# OzarkPinnacle.net
KiCad netlist of a schematic drawn in EAGLE
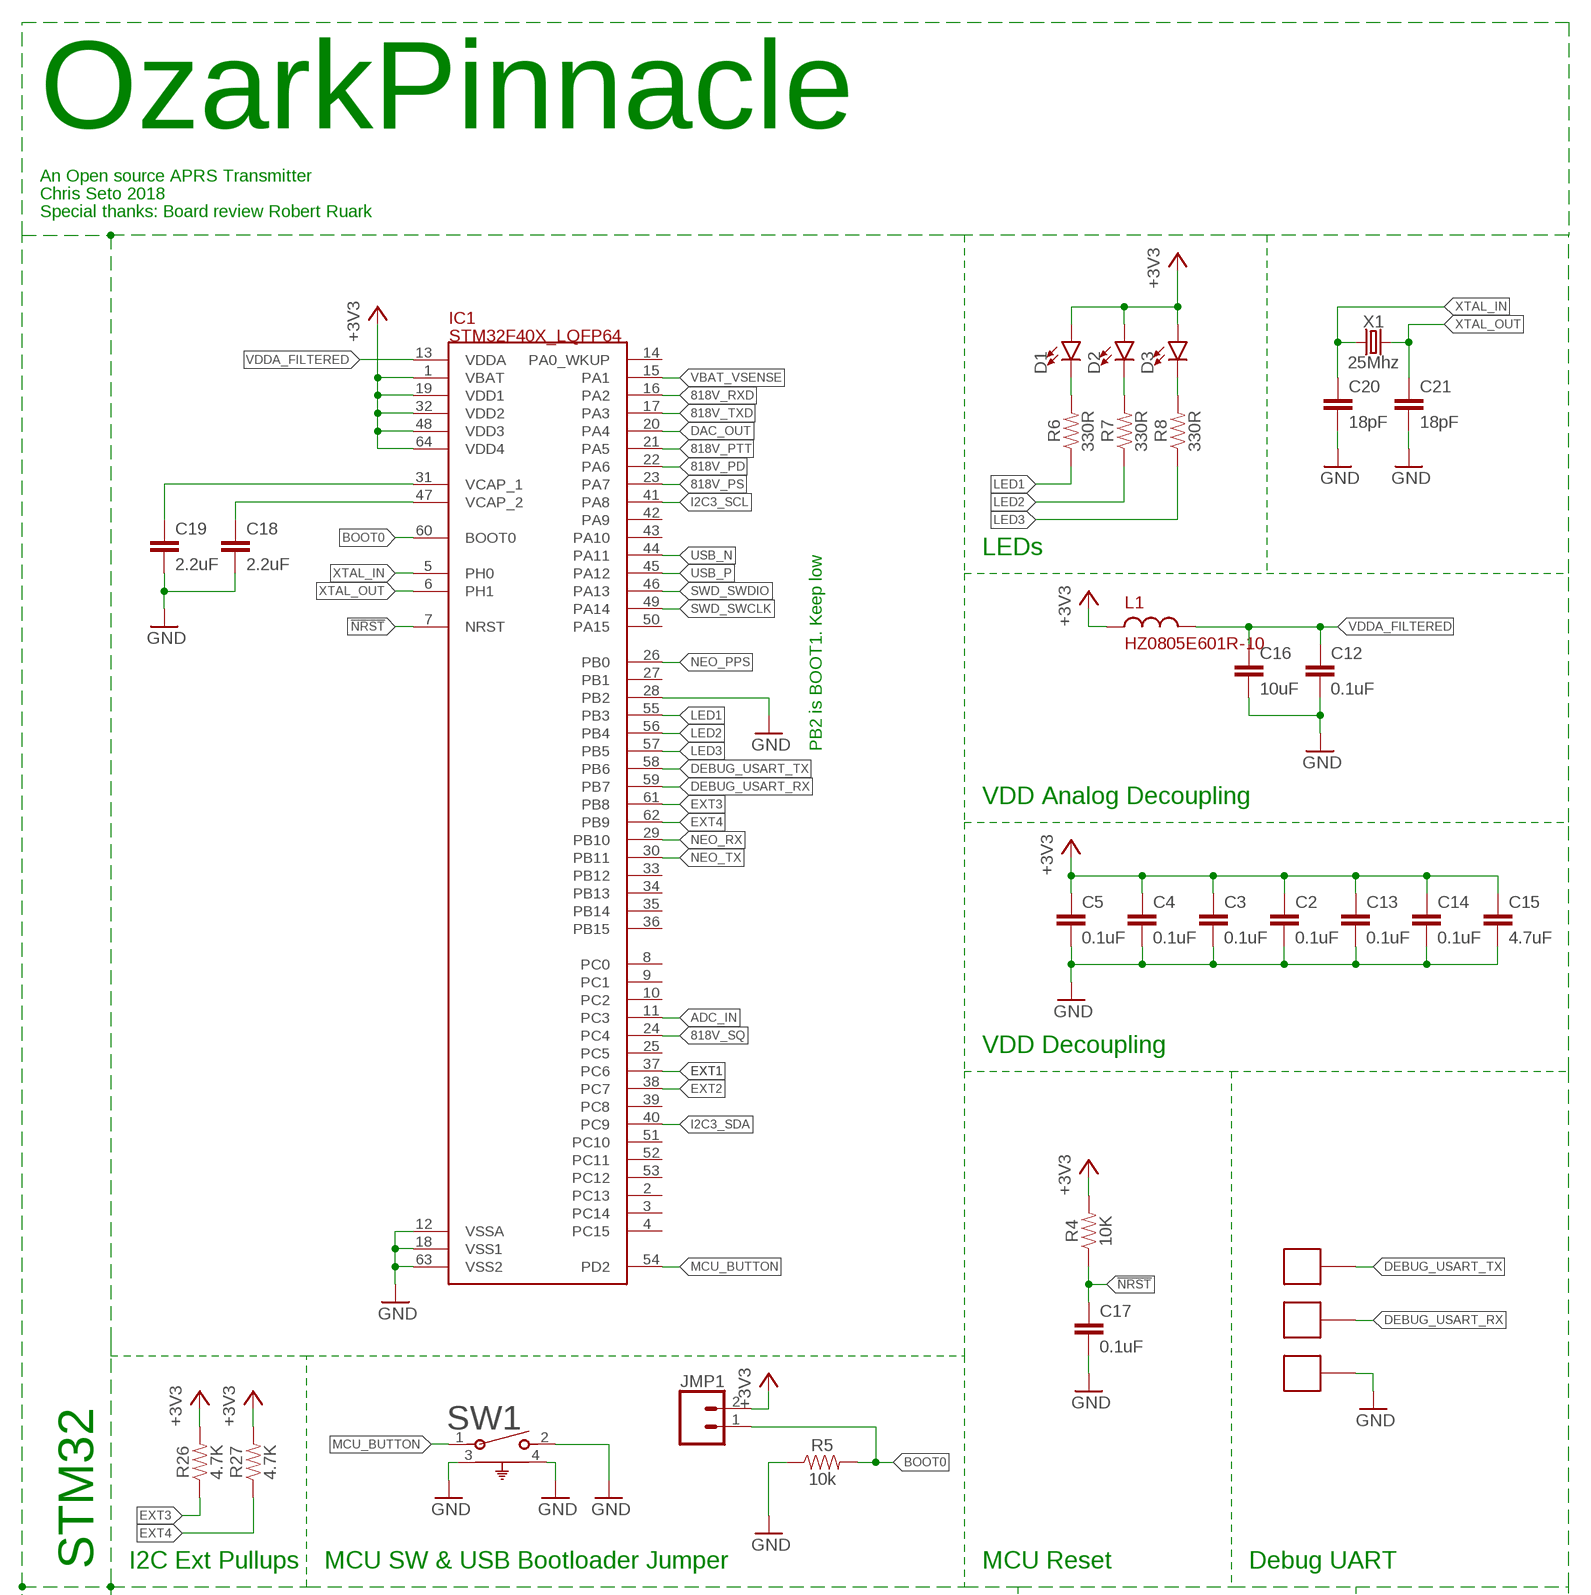
[diagram p0: schematic, sheet 1, part 1 of 2]
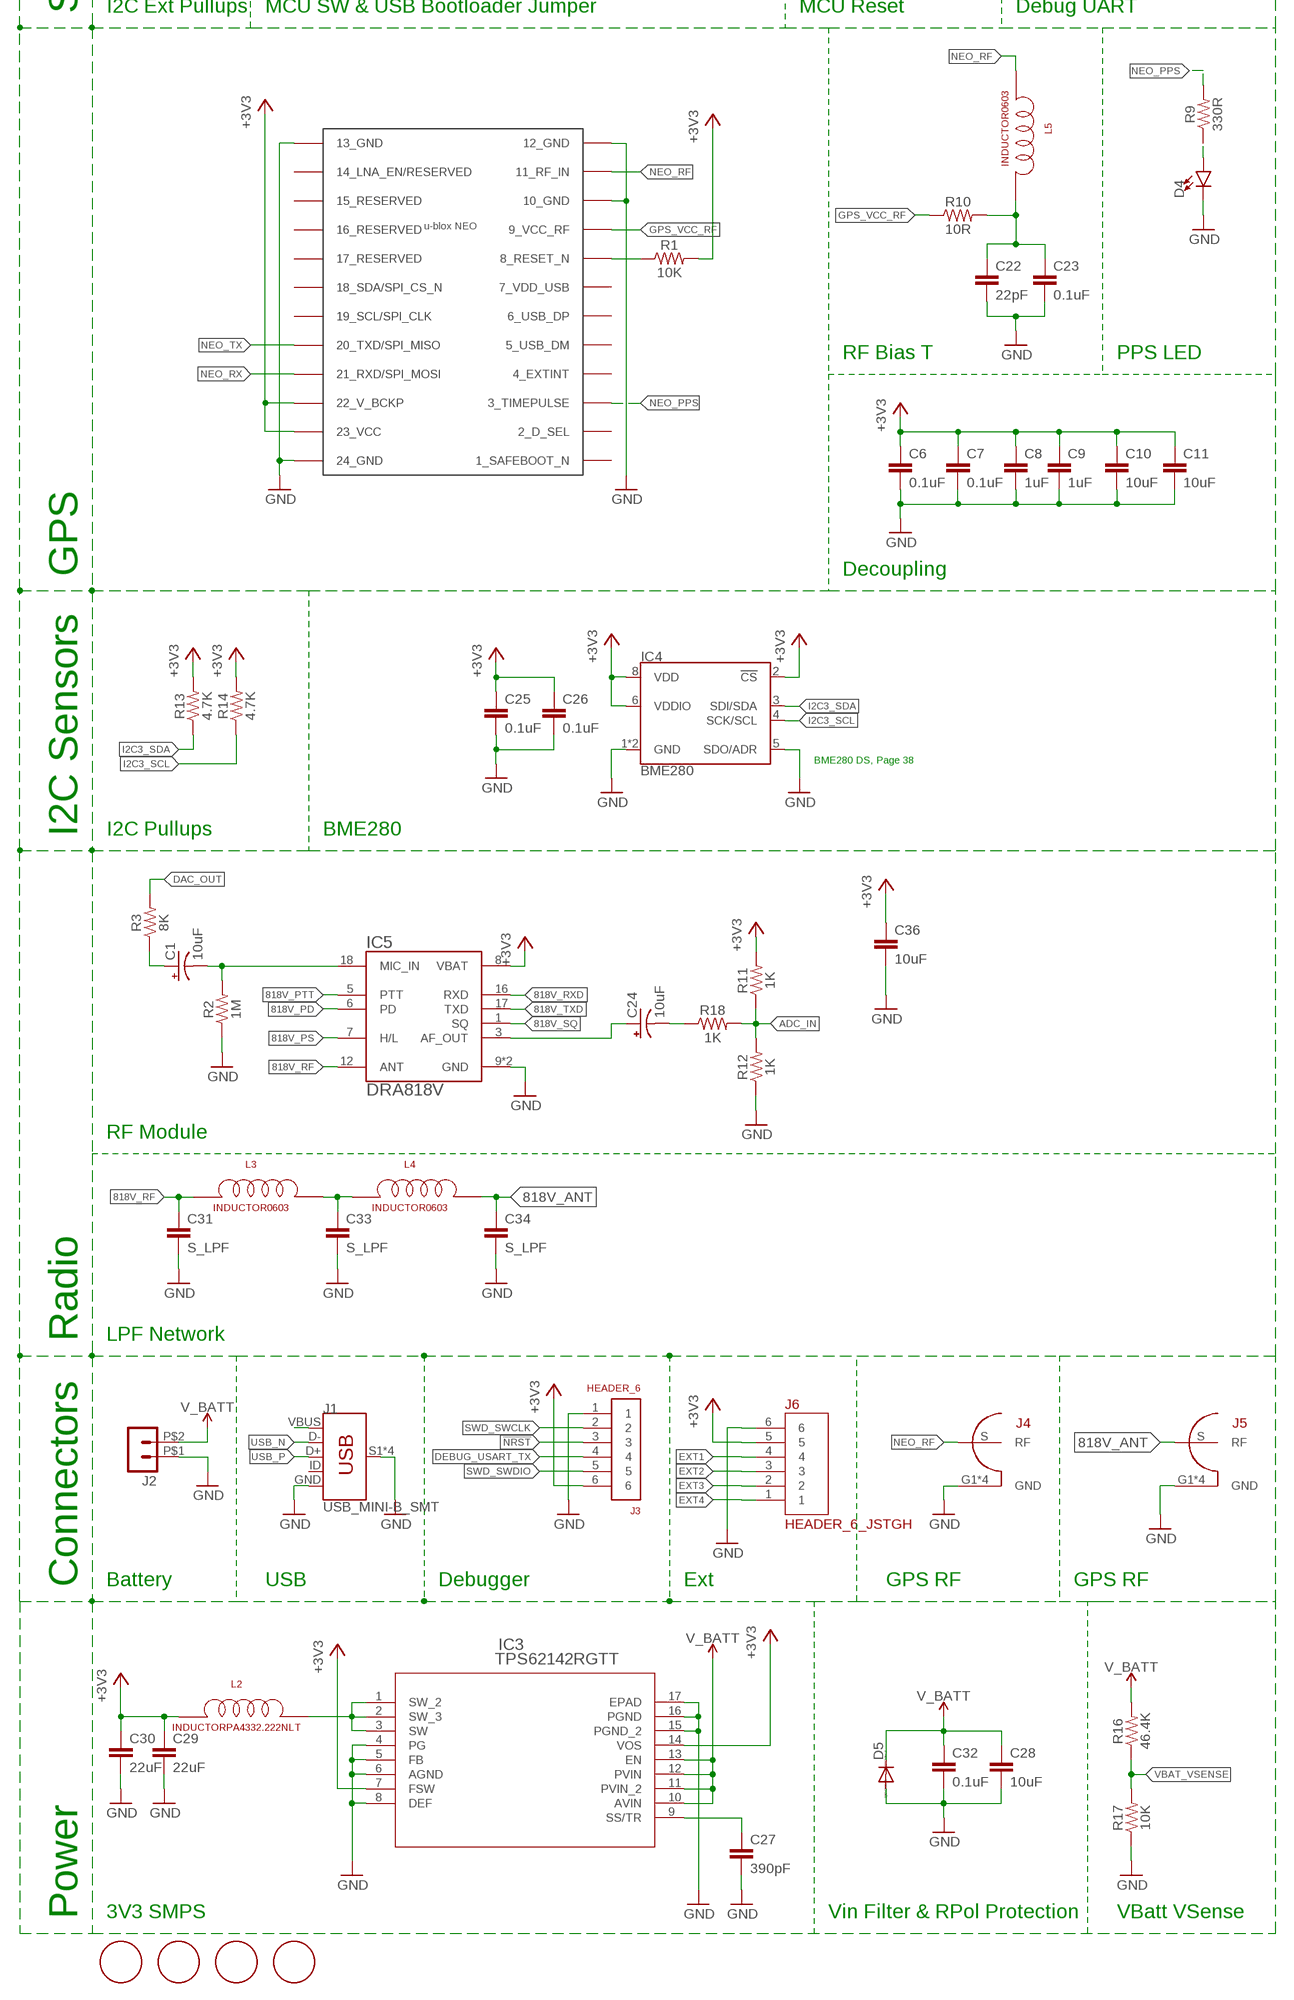
[diagram p1: schematic, sheet 1, part 2 of 2]

(export (version "E")
  (design (tool "Eeschema 10.0.6"))
  (components
    (comp (ref "C1")
      (value "10uF")
      (footprint "eagle-import:1206")
      (libsource (lib "eagle-import") (part "CAP_POL1206_POL"))
    )
    (comp (ref "C2")
      (value "0.1uF")
      (footprint "eagle-import:0603")
      (libsource (lib "eagle-import") (part "CAP0603"))
    )
    (comp (ref "C3")
      (value "0.1uF")
      (footprint "eagle-import:0603")
      (libsource (lib "eagle-import") (part "CAP0603"))
    )
    (comp (ref "C4")
      (value "0.1uF")
      (footprint "eagle-import:0603")
      (libsource (lib "eagle-import") (part "CAP0603"))
    )
    (comp (ref "C5")
      (value "0.1uF")
      (footprint "eagle-import:0603")
      (libsource (lib "eagle-import") (part "CAP0603"))
    )
    (comp (ref "C6")
      (value "0.1uF")
      (footprint "eagle-import:0603")
      (libsource (lib "eagle-import") (part "CAP0603"))
    )
    (comp (ref "C7")
      (value "0.1uF")
      (footprint "eagle-import:0603")
      (libsource (lib "eagle-import") (part "CAP0603"))
    )
    (comp (ref "C8")
      (value "1uF")
      (footprint "eagle-import:C0805")
      (libsource (lib "eagle-import") (part "C-EUC0805"))
    )
    (comp (ref "C9")
      (value "1uF")
      (footprint "eagle-import:C0805")
      (libsource (lib "eagle-import") (part "C-EUC0805"))
    )
    (comp (ref "C10")
      (value "10uF")
      (footprint "eagle-import:C0805")
      (libsource (lib "eagle-import") (part "C-EUC0805"))
    )
    (comp (ref "C11")
      (value "10uF")
      (footprint "eagle-import:C0805")
      (libsource (lib "eagle-import") (part "C-EUC0805"))
    )
    (comp (ref "C12")
      (value "0.1uF")
      (footprint "eagle-import:0603")
      (libsource (lib "eagle-import") (part "CAP0603"))
    )
    (comp (ref "C13")
      (value "0.1uF")
      (footprint "eagle-import:0603")
      (libsource (lib "eagle-import") (part "CAP0603"))
    )
    (comp (ref "C14")
      (value "0.1uF")
      (footprint "eagle-import:0603")
      (libsource (lib "eagle-import") (part "CAP0603"))
    )
    (comp (ref "C15")
      (value "4.7uF")
      (footprint "eagle-import:C0805")
      (libsource (lib "eagle-import") (part "C-EUC0805"))
    )
    (comp (ref "C16")
      (value "10uF")
      (footprint "eagle-import:C0805")
      (libsource (lib "eagle-import") (part "C-EUC0805"))
    )
    (comp (ref "C17")
      (value "0.1uF")
      (footprint "eagle-import:0603")
      (libsource (lib "eagle-import") (part "CAP0603"))
    )
    (comp (ref "C18")
      (value "2.2uF")
      (footprint "eagle-import:C0805")
      (libsource (lib "eagle-import") (part "C-EUC0805"))
    )
    (comp (ref "C19")
      (value "2.2uF")
      (footprint "eagle-import:C0805")
      (libsource (lib "eagle-import") (part "C-EUC0805"))
    )
    (comp (ref "C20")
      (value "18pF")
      (footprint "eagle-import:0603")
      (libsource (lib "eagle-import") (part "CAP0603"))
    )
    (comp (ref "C21")
      (value "18pF")
      (footprint "eagle-import:0603")
      (libsource (lib "eagle-import") (part "CAP0603"))
    )
    (comp (ref "C22")
      (value "22pF")
      (footprint "eagle-import:0603")
      (libsource (lib "eagle-import") (part "CAP0603"))
    )
    (comp (ref "C23")
      (value "0.1uF")
      (footprint "eagle-import:0603")
      (libsource (lib "eagle-import") (part "CAP0603"))
    )
    (comp (ref "C24")
      (value "10uF")
      (footprint "eagle-import:1206")
      (libsource (lib "eagle-import") (part "CAP_POL1206_POL"))
    )
    (comp (ref "C25")
      (value "0.1uF")
      (footprint "eagle-import:0603")
      (libsource (lib "eagle-import") (part "CAP0603"))
    )
    (comp (ref "C26")
      (value "0.1uF")
      (footprint "eagle-import:0603")
      (libsource (lib "eagle-import") (part "CAP0603"))
    )
    (comp (ref "C27")
      (value "390pF")
      (footprint "eagle-import:0603")
      (libsource (lib "eagle-import") (part "CAP0603"))
    )
    (comp (ref "C28")
      (value "10uF")
      (footprint "eagle-import:C0805")
      (libsource (lib "eagle-import") (part "C-EUC0805"))
    )
    (comp (ref "C29")
      (value "22uF")
      (footprint "eagle-import:1210")
      (libsource (lib "eagle-import") (part "CAP1210"))
    )
    (comp (ref "C30")
      (value "22uF")
      (footprint "eagle-import:1210")
      (libsource (lib "eagle-import") (part "CAP1210"))
    )
    (comp (ref "C31")
      (value "S_LPF")
      (footprint "eagle-import:0603")
      (libsource (lib "eagle-import") (part "CAP0603"))
    )
    (comp (ref "C32")
      (value "0.1uF")
      (footprint "eagle-import:0603")
      (libsource (lib "eagle-import") (part "CAP0603"))
    )
    (comp (ref "C33")
      (value "S_LPF")
      (footprint "eagle-import:0603")
      (libsource (lib "eagle-import") (part "CAP0603"))
    )
    (comp (ref "C34")
      (value "S_LPF")
      (footprint "eagle-import:0603")
      (libsource (lib "eagle-import") (part "CAP0603"))
    )
    (comp (ref "C36")
      (value "10uF")
      (footprint "eagle-import:C0805")
      (libsource (lib "eagle-import") (part "C-EUC0805"))
    )
    (comp (ref "D1")
      (value "LED0603")
      (footprint "eagle-import:LED-0603")
      (libsource (lib "eagle-import") (part "LED0603"))
    )
    (comp (ref "D2")
      (value "LED0603")
      (footprint "eagle-import:LED-0603")
      (libsource (lib "eagle-import") (part "LED0603"))
    )
    (comp (ref "D3")
      (value "LED0603")
      (footprint "eagle-import:LED-0603")
      (libsource (lib "eagle-import") (part "LED0603"))
    )
    (comp (ref "D4")
      (value "LED0603")
      (footprint "eagle-import:LED-0603")
      (libsource (lib "eagle-import") (part "LED0603"))
    )
    (comp (ref "D5")
      (value "DIODE-DO214AC")
      (footprint "eagle-import:DO214AC")
      (libsource (lib "eagle-import") (part "DIODE-DO214AC"))
    )
    (comp (ref "IC1")
      (value "STM32F40X_LQFP64")
      (footprint "eagle-import:STM32_LQFP64")
      (libsource (lib "eagle-import") (part "STM32F40X_LQFP64"))
    )
    (comp (ref "IC2")
      (value "NEO-M8")
      (footprint "eagle-import:NEO-M8")
      (libsource (lib "eagle-import") (part "NEO-M8"))
    )
    (comp (ref "IC3")
      (value "TPS62142RGTT")
      (footprint "eagle-import:RGT16_1P7X1P7")
      (libsource (lib "eagle-import") (part "TPS62142RGTT"))
    )
    (comp (ref "IC4")
      (value "BME280")
      (footprint "eagle-import:LGA-8-2.5X2.5")
      (libsource (lib "eagle-import") (part "BME280"))
    )
    (comp (ref "IC5")
      (value "DRA818V")
      (footprint "eagle-import:DORJI_DRA818V")
      (fields (field (name "MF") "DORJI"))
      (libsource (lib "eagle-import") (part "DRA818V"))
    )
    (comp (ref "J1")
      (value "USB_MINI-B_SMT")
      (footprint "eagle-import:USB-MINIB")
      (libsource (lib "eagle-import") (part "USB_MINI-B_SMT"))
    )
    (comp (ref "J2")
      (value "HEADER_POS2_43650-0200")
      (footprint "eagle-import:43650-0200")
      (libsource (lib "eagle-import") (part "HEADER_POS2_?43650-0200"))
    )
    (comp (ref "J3")
      (value "HEADER_6")
      (footprint "eagle-import:6X2_SMT")
      (libsource (lib "eagle-import") (part "HEADER_6"))
    )
    (comp (ref "J4")
      (value "FSK_RUARK2_SMA_0732511150")
      (footprint "eagle-import:FSK_RUARK2_WIDE_SMA")
      (libsource (lib "eagle-import") (part "FSK_RUARK2_SMA_0732511150"))
    )
    (comp (ref "J5")
      (value "FSK_RUARK2_SMA_0732511150")
      (footprint "eagle-import:FSK_RUARK2_WIDE_SMA")
      (libsource (lib "eagle-import") (part "FSK_RUARK2_SMA_0732511150"))
    )
    (comp (ref "J6")
      (value "HEADER_6_JSTGH")
      (footprint "eagle-import:BM06B-GHS-TBT(LF)(SN)(N)")
      (libsource (lib "eagle-import") (part "HEADER_6_JSTGH"))
    )
    (comp (ref "JMP1")
      (value "CONN_02")
      (footprint "eagle-import:1X02")
      (libsource (lib "eagle-import") (part "CONN_02"))
    )
    (comp (ref "L1")
      (value "HZ0805E601R-10")
      (footprint "eagle-import:R0805")
      (libsource (lib "eagle-import") (part "HZ0805E601R-10"))
    )
    (comp (ref "L2")
      (value "INDUCTORPA4332.222NLT")
      (footprint "eagle-import:PA4332.222NLT")
      (libsource (lib "eagle-import") (part "INDUCTORPA4332.222NLT"))
    )
    (comp (ref "L3")
      (value "INDUCTOR0603")
      (footprint "eagle-import:0603")
      (libsource (lib "eagle-import") (part "INDUCTOR0603"))
    )
    (comp (ref "L4")
      (value "INDUCTOR0603")
      (footprint "eagle-import:0603")
      (libsource (lib "eagle-import") (part "INDUCTOR0603"))
    )
    (comp (ref "L5")
      (value "INDUCTOR0603")
      (footprint "eagle-import:0603")
      (libsource (lib "eagle-import") (part "INDUCTOR0603"))
    )
    (comp (ref "R1")
      (value "10K")
      (footprint "eagle-import:0603")
      (libsource (lib "eagle-import") (part "RESISTOR0603"))
    )
    (comp (ref "R2")
      (value "1M")
      (footprint "eagle-import:0603")
      (libsource (lib "eagle-import") (part "RESISTOR0603"))
    )
    (comp (ref "R3")
      (value "8K")
      (footprint "eagle-import:0603")
      (libsource (lib "eagle-import") (part "RESISTOR0603"))
    )
    (comp (ref "R4")
      (value "10K")
      (footprint "eagle-import:0603")
      (libsource (lib "eagle-import") (part "RESISTOR0603"))
    )
    (comp (ref "R5")
      (value "10k")
      (footprint "eagle-import:0603")
      (libsource (lib "eagle-import") (part "RESISTOR0603"))
    )
    (comp (ref "R6")
      (value "330R")
      (footprint "eagle-import:0603")
      (libsource (lib "eagle-import") (part "RESISTOR0603"))
    )
    (comp (ref "R7")
      (value "330R")
      (footprint "eagle-import:0603")
      (libsource (lib "eagle-import") (part "RESISTOR0603"))
    )
    (comp (ref "R8")
      (value "330R")
      (footprint "eagle-import:0603")
      (libsource (lib "eagle-import") (part "RESISTOR0603"))
    )
    (comp (ref "R9")
      (value "330R")
      (footprint "eagle-import:0603")
      (libsource (lib "eagle-import") (part "RESISTOR0603"))
    )
    (comp (ref "R10")
      (value "10R")
      (footprint "eagle-import:0603")
      (libsource (lib "eagle-import") (part "RESISTOR0603"))
    )
    (comp (ref "R11")
      (value "1K")
      (footprint "eagle-import:0603")
      (libsource (lib "eagle-import") (part "RESISTOR0603"))
    )
    (comp (ref "R12")
      (value "1K")
      (footprint "eagle-import:0603")
      (libsource (lib "eagle-import") (part "RESISTOR0603"))
    )
    (comp (ref "R13")
      (value "4.7K")
      (footprint "eagle-import:0603")
      (libsource (lib "eagle-import") (part "RESISTOR0603"))
    )
    (comp (ref "R14")
      (value "4.7K")
      (footprint "eagle-import:0603")
      (libsource (lib "eagle-import") (part "RESISTOR0603"))
    )
    (comp (ref "R16")
      (value "46.4K")
      (footprint "eagle-import:0603")
      (libsource (lib "eagle-import") (part "RESISTOR0603"))
    )
    (comp (ref "R17")
      (value "10K")
      (footprint "eagle-import:0603")
      (libsource (lib "eagle-import") (part "RESISTOR0603"))
    )
    (comp (ref "R18")
      (value "1K")
      (footprint "eagle-import:0603")
      (libsource (lib "eagle-import") (part "RESISTOR0603"))
    )
    (comp (ref "R26")
      (value "4.7K")
      (footprint "eagle-import:0603")
      (libsource (lib "eagle-import") (part "RESISTOR0603"))
    )
    (comp (ref "R27")
      (value "4.7K")
      (footprint "eagle-import:0603")
      (libsource (lib "eagle-import") (part "RESISTOR0603"))
    )
    (comp (ref "SW1")
      (value "1825027-8")
      (footprint "eagle-import:SW2_1825027-C")
      (fields (field (name "MANUFACTURER_PART_NUMBER") "18250278"))
      (libsource (lib "eagle-import") (part "1825027-8"))
    )
    (comp (ref "U$2")
      (value "SINGLEPADMIDPAD")
      (footprint "eagle-import:MIDPAD")
      (libsource (lib "eagle-import") (part "SINGLEPADMIDPAD"))
    )
    (comp (ref "U$3")
      (value "SINGLEPADMIDPAD")
      (footprint "eagle-import:MIDPAD")
      (libsource (lib "eagle-import") (part "SINGLEPADMIDPAD"))
    )
    (comp (ref "U$4")
      (value "SINGLEPADMIDPAD")
      (footprint "eagle-import:MIDPAD")
      (libsource (lib "eagle-import") (part "SINGLEPADMIDPAD"))
    )
    (comp (ref "U$7")
      (value "MOUNTING_HOLE#2")
      (footprint "eagle-import:#2_CLEARANCE_HOLE")
      (libsource (lib "eagle-import") (part "MOUNTING_HOLE#2"))
    )
    (comp (ref "U$8")
      (value "MOUNTING_HOLE#2")
      (footprint "eagle-import:#2_CLEARANCE_HOLE")
      (libsource (lib "eagle-import") (part "MOUNTING_HOLE#2"))
    )
    (comp (ref "U$9")
      (value "MOUNTING_HOLE#2")
      (footprint "eagle-import:#2_CLEARANCE_HOLE")
      (libsource (lib "eagle-import") (part "MOUNTING_HOLE#2"))
    )
    (comp (ref "U$10")
      (value "MOUNTING_HOLE#2")
      (footprint "eagle-import:#2_CLEARANCE_HOLE")
      (libsource (lib "eagle-import") (part "MOUNTING_HOLE#2"))
    )
    (comp (ref "X1")
      (value "25Mhz")
      (footprint "eagle-import:CRYSTAL-SMD-3.2X2.5MM")
      (libsource (lib "eagle-import") (part "CRYSTALSMD-3.2X2.5"))
    )
  )
  (nets
    (net (code "1") (name "+3V3") (class "Default")
      (node (ref "C10") (pin "1") (pinfunction "1_1") (pintype "passive"))
      (node (ref "C11") (pin "1") (pinfunction "1_1") (pintype "passive"))
      (node (ref "C13") (pin "1") (pinfunction "1_1") (pintype "passive"))
      (node (ref "C14") (pin "1") (pinfunction "1_1") (pintype "passive"))
      (node (ref "C15") (pin "1") (pinfunction "1_1") (pintype "passive"))
      (node (ref "C2") (pin "1") (pinfunction "1_1") (pintype "passive"))
      (node (ref "C25") (pin "1") (pinfunction "1_1") (pintype "passive"))
      (node (ref "C26") (pin "1") (pinfunction "1_1") (pintype "passive"))
      (node (ref "C29") (pin "1") (pinfunction "1_1") (pintype "passive"))
      (node (ref "C3") (pin "1") (pinfunction "1_1") (pintype "passive"))
      (node (ref "C30") (pin "1") (pinfunction "1_1") (pintype "passive"))
      (node (ref "C36") (pin "1") (pinfunction "1_1") (pintype "passive"))
      (node (ref "C4") (pin "1") (pinfunction "1_1") (pintype "passive"))
      (node (ref "C5") (pin "1") (pinfunction "1_1") (pintype "passive"))
      (node (ref "C6") (pin "1") (pinfunction "1_1") (pintype "passive"))
      (node (ref "C7") (pin "1") (pinfunction "1_1") (pintype "passive"))
      (node (ref "C8") (pin "1") (pinfunction "1_1") (pintype "passive"))
      (node (ref "C9") (pin "1") (pinfunction "1_1") (pintype "passive"))
      (node (ref "D1") (pin "A") (pinfunction "A_A") (pintype "passive"))
      (node (ref "D2") (pin "A") (pinfunction "A_A") (pintype "passive"))
      (node (ref "D3") (pin "A") (pinfunction "A_A") (pintype "passive"))
      (node (ref "IC1") (pin "1") (pinfunction "VBAT_1") (pintype "bidirectional"))
      (node (ref "IC1") (pin "19") (pinfunction "VDD1_19") (pintype "bidirectional"))
      (node (ref "IC1") (pin "32") (pinfunction "VDD2_32") (pintype "bidirectional"))
      (node (ref "IC1") (pin "48") (pinfunction "VDD3_48") (pintype "bidirectional"))
      (node (ref "IC1") (pin "64") (pinfunction "VDD4_64") (pintype "bidirectional"))
      (node (ref "IC2") (pin "22") (pinfunction "22_V_BCKP_22") (pintype "bidirectional"))
      (node (ref "IC2") (pin "23") (pinfunction "23_VCC_23") (pintype "bidirectional"))
      (node (ref "IC3") (pin "14") (pinfunction "VOS_14") (pintype "input"))
      (node (ref "IC3") (pin "7") (pinfunction "FSW_7") (pintype "input"))
      (node (ref "IC4") (pin "2") (pinfunction "~{CS}_2") (pintype "bidirectional"))
      (node (ref "IC4") (pin "6") (pinfunction "VDDIO_6") (pintype "bidirectional"))
      (node (ref "IC4") (pin "8") (pinfunction "VDD_8") (pintype "bidirectional"))
      (node (ref "IC5") (pin "8") (pinfunction "VBAT_8") (pintype "power_in"))
      (node (ref "J3") (pin "6") (pinfunction "6_6") (pintype "bidirectional"))
      (node (ref "J6") (pin "5") (pinfunction "5_5") (pintype "bidirectional"))
      (node (ref "JMP1") (pin "2") (pinfunction "2_2") (pintype "passive"))
      (node (ref "L1") (pin "1") (pinfunction "1_1") (pintype "passive"))
      (node (ref "L2") (pin "1") (pinfunction "1_1") (pintype "power_in"))
      (node (ref "R1") (pin "2") (pinfunction "2_2") (pintype "passive"))
      (node (ref "R11") (pin "2") (pinfunction "2_2") (pintype "passive"))
      (node (ref "R13") (pin "2") (pinfunction "2_2") (pintype "passive"))
      (node (ref "R14") (pin "2") (pinfunction "2_2") (pintype "passive"))
      (node (ref "R26") (pin "2") (pinfunction "2_2") (pintype "passive"))
      (node (ref "R27") (pin "2") (pinfunction "2_2") (pintype "passive"))
      (node (ref "R4") (pin "2") (pinfunction "2_2") (pintype "passive"))
    )
    (net (code "2") (name "/~{NRST}") (class "Default")
      (node (ref "C17") (pin "1") (pinfunction "1_1") (pintype "passive"))
      (node (ref "IC1") (pin "7") (pinfunction "NRST_7") (pintype "bidirectional"))
      (node (ref "J3") (pin "3") (pinfunction "3_3") (pintype "bidirectional"))
      (node (ref "R4") (pin "1") (pinfunction "1_1") (pintype "passive"))
    )
    (net (code "3") (name "818V_ANT") (class "Default")
      (node (ref "C34") (pin "1") (pinfunction "1_1") (pintype "passive"))
      (node (ref "J5") (pin "S") (pinfunction "RF_S") (pintype "bidirectional"))
      (node (ref "L4") (pin "2") (pinfunction "2_2") (pintype "power_in"))
    )
    (net (code "4") (name "818V_PD") (class "Default")
      (node (ref "IC1") (pin "22") (pinfunction "PA6_22") (pintype "bidirectional"))
      (node (ref "IC5") (pin "6") (pinfunction "PD_6") (pintype "input"))
    )
    (net (code "5") (name "818V_PS") (class "Default")
      (node (ref "IC1") (pin "23") (pinfunction "PA7_23") (pintype "bidirectional"))
      (node (ref "IC5") (pin "7") (pinfunction "H/L_7") (pintype "input"))
    )
    (net (code "6") (name "818V_PTT") (class "Default")
      (node (ref "IC1") (pin "21") (pinfunction "PA5_21") (pintype "bidirectional"))
      (node (ref "IC5") (pin "5") (pinfunction "PTT_5") (pintype "input"))
    )
    (net (code "7") (name "818V_RF") (class "Default")
      (node (ref "C31") (pin "1") (pinfunction "1_1") (pintype "passive"))
      (node (ref "IC5") (pin "12") (pinfunction "ANT_12") (pintype "passive"))
      (node (ref "L3") (pin "1") (pinfunction "1_1") (pintype "power_in"))
    )
    (net (code "8") (name "818V_RXD") (class "Default")
      (node (ref "IC1") (pin "16") (pinfunction "PA2_16") (pintype "bidirectional"))
      (node (ref "IC5") (pin "16") (pinfunction "RXD_16") (pintype "input"))
    )
    (net (code "9") (name "818V_SQ") (class "Default")
      (node (ref "IC1") (pin "24") (pinfunction "PC4_24") (pintype "bidirectional"))
      (node (ref "IC5") (pin "1") (pinfunction "SQ_1") (pintype "output"))
    )
    (net (code "10") (name "818V_TXD") (class "Default")
      (node (ref "IC1") (pin "17") (pinfunction "PA3_17") (pintype "bidirectional"))
      (node (ref "IC5") (pin "17") (pinfunction "TXD_17") (pintype "output"))
    )
    (net (code "11") (name "ADC_IN") (class "Default")
      (node (ref "IC1") (pin "11") (pinfunction "PC3_11") (pintype "bidirectional"))
      (node (ref "R11") (pin "1") (pinfunction "1_1") (pintype "passive"))
      (node (ref "R12") (pin "2") (pinfunction "2_2") (pintype "passive"))
      (node (ref "R18") (pin "2") (pinfunction "2_2") (pintype "passive"))
    )
    (net (code "12") (name "BOOT0") (class "Default")
      (node (ref "IC1") (pin "60") (pinfunction "BOOT0_60") (pintype "bidirectional"))
      (node (ref "JMP1") (pin "1") (pinfunction "1_1") (pintype "passive"))
      (node (ref "R5") (pin "2") (pinfunction "2_2") (pintype "passive"))
    )
    (net (code "13") (name "DAC_OUT") (class "Default")
      (node (ref "IC1") (pin "20") (pinfunction "PA4_20") (pintype "bidirectional"))
      (node (ref "R3") (pin "2") (pinfunction "2_2") (pintype "passive"))
    )
    (net (code "14") (name "DEBUG_USART_RX") (class "Default")
      (node (ref "IC1") (pin "59") (pinfunction "PB7_59") (pintype "bidirectional"))
      (node (ref "U$3") (pin "1") (pinfunction "1_1") (pintype "bidirectional"))
    )
    (net (code "15") (name "DEBUG_USART_TX") (class "Default")
      (node (ref "IC1") (pin "58") (pinfunction "PB6_58") (pintype "bidirectional"))
      (node (ref "J3") (pin "4") (pinfunction "4_4") (pintype "bidirectional"))
      (node (ref "U$2") (pin "1") (pinfunction "1_1") (pintype "bidirectional"))
    )
    (net (code "16") (name "EXT1") (class "Default")
      (node (ref "IC1") (pin "37") (pinfunction "PC6_37") (pintype "bidirectional"))
      (node (ref "J6") (pin "4") (pinfunction "4_4") (pintype "bidirectional"))
    )
    (net (code "17") (name "EXT2") (class "Default")
      (node (ref "IC1") (pin "38") (pinfunction "PC7_38") (pintype "bidirectional"))
      (node (ref "J6") (pin "3") (pinfunction "3_3") (pintype "bidirectional"))
    )
    (net (code "18") (name "EXT3") (class "Default")
      (node (ref "IC1") (pin "61") (pinfunction "PB8_61") (pintype "bidirectional"))
      (node (ref "J6") (pin "2") (pinfunction "2_2") (pintype "bidirectional"))
      (node (ref "R26") (pin "1") (pinfunction "1_1") (pintype "passive"))
    )
    (net (code "19") (name "EXT4") (class "Default")
      (node (ref "IC1") (pin "62") (pinfunction "PB9_62") (pintype "bidirectional"))
      (node (ref "J6") (pin "1") (pinfunction "1_1") (pintype "bidirectional"))
      (node (ref "R27") (pin "1") (pinfunction "1_1") (pintype "passive"))
    )
    (net (code "20") (name "GND") (class "Default")
      (node (ref "C10") (pin "2") (pinfunction "2_2") (pintype "passive"))
      (node (ref "C11") (pin "2") (pinfunction "2_2") (pintype "passive"))
      (node (ref "C12") (pin "2") (pinfunction "2_2") (pintype "passive"))
      (node (ref "C13") (pin "2") (pinfunction "2_2") (pintype "passive"))
      (node (ref "C14") (pin "2") (pinfunction "2_2") (pintype "passive"))
      (node (ref "C15") (pin "2") (pinfunction "2_2") (pintype "passive"))
      (node (ref "C16") (pin "2") (pinfunction "2_2") (pintype "passive"))
      (node (ref "C17") (pin "2") (pinfunction "2_2") (pintype "passive"))
      (node (ref "C18") (pin "2") (pinfunction "2_2") (pintype "passive"))
      (node (ref "C19") (pin "2") (pinfunction "2_2") (pintype "passive"))
      (node (ref "C2") (pin "2") (pinfunction "2_2") (pintype "passive"))
      (node (ref "C20") (pin "2") (pinfunction "2_2") (pintype "passive"))
      (node (ref "C21") (pin "2") (pinfunction "2_2") (pintype "passive"))
      (node (ref "C22") (pin "2") (pinfunction "2_2") (pintype "passive"))
      (node (ref "C23") (pin "2") (pinfunction "2_2") (pintype "passive"))
      (node (ref "C25") (pin "2") (pinfunction "2_2") (pintype "passive"))
      (node (ref "C26") (pin "2") (pinfunction "2_2") (pintype "passive"))
      (node (ref "C27") (pin "2") (pinfunction "2_2") (pintype "passive"))
      (node (ref "C28") (pin "2") (pinfunction "2_2") (pintype "passive"))
      (node (ref "C29") (pin "2") (pinfunction "2_2") (pintype "passive"))
      (node (ref "C3") (pin "2") (pinfunction "2_2") (pintype "passive"))
      (node (ref "C30") (pin "2") (pinfunction "2_2") (pintype "passive"))
      (node (ref "C31") (pin "2") (pinfunction "2_2") (pintype "passive"))
      (node (ref "C32") (pin "2") (pinfunction "2_2") (pintype "passive"))
      (node (ref "C33") (pin "2") (pinfunction "2_2") (pintype "passive"))
      (node (ref "C34") (pin "2") (pinfunction "2_2") (pintype "passive"))
      (node (ref "C36") (pin "2") (pinfunction "2_2") (pintype "passive"))
      (node (ref "C4") (pin "2") (pinfunction "2_2") (pintype "passive"))
      (node (ref "C5") (pin "2") (pinfunction "2_2") (pintype "passive"))
      (node (ref "C6") (pin "2") (pinfunction "2_2") (pintype "passive"))
      (node (ref "C7") (pin "2") (pinfunction "2_2") (pintype "passive"))
      (node (ref "C8") (pin "2") (pinfunction "2_2") (pintype "passive"))
      (node (ref "C9") (pin "2") (pinfunction "2_2") (pintype "passive"))
      (node (ref "D4") (pin "C") (pinfunction "C_C") (pintype "passive"))
      (node (ref "D5") (pin "A") (pinfunction "A_A") (pintype "passive"))
      (node (ref "IC1") (pin "12") (pinfunction "VSSA_12") (pintype "bidirectional"))
      (node (ref "IC1") (pin "18") (pinfunction "VSS1_18") (pintype "bidirectional"))
      (node (ref "IC1") (pin "28") (pinfunction "PB2_28") (pintype "bidirectional"))
      (node (ref "IC1") (pin "63") (pinfunction "VSS2_63") (pintype "bidirectional"))
      (node (ref "IC2") (pin "10") (pinfunction "10_GND_10") (pintype "bidirectional"))
      (node (ref "IC2") (pin "12") (pinfunction "12_GND_12") (pintype "bidirectional"))
      (node (ref "IC2") (pin "13") (pinfunction "13_GND_13") (pintype "bidirectional"))
      (node (ref "IC2") (pin "24") (pinfunction "24_GND_24") (pintype "bidirectional"))
      (node (ref "IC3") (pin "15") (pinfunction "PGND_2_15") (pintype "power_in"))
      (node (ref "IC3") (pin "16") (pinfunction "PGND_16") (pintype "power_in"))
      (node (ref "IC3") (pin "17") (pinfunction "EPAD_17") (pintype "passive"))
      (node (ref "IC3") (pin "4") (pinfunction "PG_4") (pintype "output"))
      (node (ref "IC3") (pin "5") (pinfunction "FB_5") (pintype "input"))
      (node (ref "IC3") (pin "6") (pinfunction "AGND_6") (pintype "power_in"))
      (node (ref "IC3") (pin "8") (pinfunction "DEF_8") (pintype "input"))
      (node (ref "IC4") (pin "1") (pinfunction "GND_1") (pintype "bidirectional"))
      (node (ref "IC4") (pin "5") (pinfunction "SDO/ADR_5") (pintype "bidirectional"))
      (node (ref "IC4") (pin "7") (pinfunction "GND_7") (pintype "bidirectional"))
      (node (ref "IC5") (pin "10") (pinfunction "GND_10") (pintype "power_in"))
      (node (ref "IC5") (pin "9") (pinfunction "GND_9") (pintype "power_in"))
      (node (ref "J1") (pin "GND") (pinfunction "GND_GND") (pintype "power_in"))
      (node (ref "J1") (pin "S1") (pinfunction "SHIELD_S1") (pintype "bidirectional"))
      (node (ref "J1") (pin "S2") (pinfunction "SHIELD_S2") (pintype "bidirectional"))
      (node (ref "J1") (pin "S3") (pinfunction "SHIELD_S3") (pintype "bidirectional"))
      (node (ref "J1") (pin "S4") (pinfunction "SHIELD_S4") (pintype "bidirectional"))
      (node (ref "J2") (pin "P$1") (pinfunction "1_P$1") (pintype "passive"))
      (node (ref "J3") (pin "1") (pinfunction "1_1") (pintype "bidirectional"))
      (node (ref "J4") (pin "G1") (pinfunction "GND_G1") (pintype "bidirectional"))
      (node (ref "J4") (pin "G2") (pinfunction "GND_G2") (pintype "bidirectional"))
      (node (ref "J4") (pin "G3") (pinfunction "GND_G3") (pintype "bidirectional"))
      (node (ref "J4") (pin "G4") (pinfunction "GND_G4") (pintype "bidirectional"))
      (node (ref "J5") (pin "G1") (pinfunction "GND_G1") (pintype "bidirectional"))
      (node (ref "J5") (pin "G2") (pinfunction "GND_G2") (pintype "bidirectional"))
      (node (ref "J5") (pin "G3") (pinfunction "GND_G3") (pintype "bidirectional"))
      (node (ref "J5") (pin "G4") (pinfunction "GND_G4") (pintype "bidirectional"))
      (node (ref "J6") (pin "6") (pinfunction "6_6") (pintype "bidirectional"))
      (node (ref "R12") (pin "1") (pinfunction "1_1") (pintype "passive"))
      (node (ref "R17") (pin "1") (pinfunction "1_1") (pintype "passive"))
      (node (ref "R2") (pin "1") (pinfunction "1_1") (pintype "passive"))
      (node (ref "R5") (pin "1") (pinfunction "1_1") (pintype "passive"))
      (node (ref "SW1") (pin "2") (pinfunction "2_2") (pintype "passive"))
      (node (ref "SW1") (pin "3") (pinfunction "3_3") (pintype "passive"))
      (node (ref "SW1") (pin "4") (pinfunction "4_4") (pintype "passive"))
      (node (ref "U$4") (pin "1") (pinfunction "1_1") (pintype "bidirectional"))
    )
    (net (code "21") (name "GPS_VCC_RF") (class "Default")
      (node (ref "IC2") (pin "9") (pinfunction "9_VCC_RF_9") (pintype "bidirectional"))
      (node (ref "R10") (pin "1") (pinfunction "1_1") (pintype "passive"))
    )
    (net (code "22") (name "I2C3_SCL") (class "Default")
      (node (ref "IC1") (pin "41") (pinfunction "PA8_41") (pintype "bidirectional"))
      (node (ref "IC4") (pin "4") (pinfunction "SCK/SCL_4") (pintype "bidirectional"))
      (node (ref "R14") (pin "1") (pinfunction "1_1") (pintype "passive"))
    )
    (net (code "23") (name "I2C3_SDA") (class "Default")
      (node (ref "IC1") (pin "40") (pinfunction "PC9_40") (pintype "bidirectional"))
      (node (ref "IC4") (pin "3") (pinfunction "SDI/SDA_3") (pintype "bidirectional"))
      (node (ref "R13") (pin "1") (pinfunction "1_1") (pintype "passive"))
    )
    (net (code "24") (name "LED1") (class "Default")
      (node (ref "IC1") (pin "55") (pinfunction "PB3_55") (pintype "bidirectional"))
      (node (ref "R6") (pin "1") (pinfunction "1_1") (pintype "passive"))
    )
    (net (code "25") (name "LED2") (class "Default")
      (node (ref "IC1") (pin "56") (pinfunction "PB4_56") (pintype "bidirectional"))
      (node (ref "R7") (pin "1") (pinfunction "1_1") (pintype "passive"))
    )
    (net (code "26") (name "LED3") (class "Default")
      (node (ref "IC1") (pin "57") (pinfunction "PB5_57") (pintype "bidirectional"))
      (node (ref "R8") (pin "1") (pinfunction "1_1") (pintype "passive"))
    )
    (net (code "27") (name "MCU_BUTTON") (class "Default")
      (node (ref "IC1") (pin "54") (pinfunction "PD2_54") (pintype "bidirectional"))
      (node (ref "SW1") (pin "1") (pinfunction "1_1") (pintype "passive"))
    )
    (net (code "28") (name "NEO_PPS") (class "Default")
      (node (ref "IC1") (pin "26") (pinfunction "PB0_26") (pintype "bidirectional"))
      (node (ref "IC2") (pin "3") (pinfunction "3_TIMEPULSE_3") (pintype "bidirectional"))
      (node (ref "R9") (pin "2") (pinfunction "2_2") (pintype "passive"))
    )
    (net (code "29") (name "NEO_RF") (class "Default")
      (node (ref "IC2") (pin "11") (pinfunction "11_RF_IN_11") (pintype "bidirectional"))
      (node (ref "J4") (pin "S") (pinfunction "RF_S") (pintype "bidirectional"))
      (node (ref "L5") (pin "1") (pinfunction "1_1") (pintype "power_in"))
    )
    (net (code "30") (name "NEO_RX") (class "Default")
      (node (ref "IC1") (pin "29") (pinfunction "PB10_29") (pintype "bidirectional"))
      (node (ref "IC2") (pin "21") (pinfunction "21_RXD/SPI_MOSI_21") (pintype "bidirectional"))
    )
    (net (code "31") (name "NEO_TX") (class "Default")
      (node (ref "IC1") (pin "30") (pinfunction "PB11_30") (pintype "bidirectional"))
      (node (ref "IC2") (pin "20") (pinfunction "20_TXD/SPI_MISO_20") (pintype "bidirectional"))
    )
    (net (code "32") (name "Net-(C1-+)") (class "Default")
      (node (ref "C1") (pin "1") (pinfunction "+_1") (pintype "passive"))
      (node (ref "R3") (pin "1") (pinfunction "1_1") (pintype "passive"))
    )
    (net (code "33") (name "Net-(C1--)") (class "Default")
      (node (ref "C1") (pin "2") (pinfunction "-_2") (pintype "passive"))
      (node (ref "IC5") (pin "18") (pinfunction "MIC_IN_18") (pintype "input"))
      (node (ref "R2") (pin "2") (pinfunction "2_2") (pintype "passive"))
    )
    (net (code "34") (name "Net-(C22-Pad1)") (class "Default")
      (node (ref "C22") (pin "1") (pinfunction "1_1") (pintype "passive"))
      (node (ref "C23") (pin "1") (pinfunction "1_1") (pintype "passive"))
      (node (ref "L5") (pin "2") (pinfunction "2_2") (pintype "power_in"))
      (node (ref "R10") (pin "2") (pinfunction "2_2") (pintype "passive"))
    )
    (net (code "35") (name "Net-(C24-+)") (class "Default")
      (node (ref "C24") (pin "1") (pinfunction "+_1") (pintype "passive"))
      (node (ref "IC5") (pin "3") (pinfunction "AF_OUT_3") (pintype "output"))
    )
    (net (code "36") (name "Net-(C24--)") (class "Default")
      (node (ref "C24") (pin "2") (pinfunction "-_2") (pintype "passive"))
      (node (ref "R18") (pin "1") (pinfunction "1_1") (pintype "passive"))
    )
    (net (code "37") (name "Net-(C33-Pad1)") (class "Default")
      (node (ref "C33") (pin "1") (pinfunction "1_1") (pintype "passive"))
      (node (ref "L3") (pin "2") (pinfunction "2_2") (pintype "power_in"))
      (node (ref "L4") (pin "1") (pinfunction "1_1") (pintype "power_in"))
    )
    (net (code "38") (name "Net-(D1-PadC)") (class "Default")
      (node (ref "D1") (pin "C") (pinfunction "C_C") (pintype "passive"))
      (node (ref "R6") (pin "2") (pinfunction "2_2") (pintype "passive"))
    )
    (net (code "39") (name "Net-(D2-PadC)") (class "Default")
      (node (ref "D2") (pin "C") (pinfunction "C_C") (pintype "passive"))
      (node (ref "R7") (pin "2") (pinfunction "2_2") (pintype "passive"))
    )
    (net (code "40") (name "Net-(D3-PadC)") (class "Default")
      (node (ref "D3") (pin "C") (pinfunction "C_C") (pintype "passive"))
      (node (ref "R8") (pin "2") (pinfunction "2_2") (pintype "passive"))
    )
    (net (code "41") (name "Net-(D4-PadA)") (class "Default")
      (node (ref "D4") (pin "A") (pinfunction "A_A") (pintype "passive"))
      (node (ref "R9") (pin "1") (pinfunction "1_1") (pintype "passive"))
    )
    (net (code "42") (name "Net-(IC1-VCAP_1)") (class "Default")
      (node (ref "C19") (pin "1") (pinfunction "1_1") (pintype "passive"))
      (node (ref "IC1") (pin "31") (pinfunction "VCAP_1_31") (pintype "bidirectional"))
    )
    (net (code "43") (name "Net-(IC1-VCAP_2)") (class "Default")
      (node (ref "C18") (pin "1") (pinfunction "1_1") (pintype "passive"))
      (node (ref "IC1") (pin "47") (pinfunction "VCAP_2_47") (pintype "bidirectional"))
    )
    (net (code "44") (name "Net-(IC2-8_RESET_N)") (class "Default")
      (node (ref "IC2") (pin "8") (pinfunction "8_RESET_N_8") (pintype "bidirectional"))
      (node (ref "R1") (pin "1") (pinfunction "1_1") (pintype "passive"))
    )
    (net (code "45") (name "Net-(IC3-SS{slash}TR)") (class "Default")
      (node (ref "C27") (pin "1") (pinfunction "1_1") (pintype "passive"))
      (node (ref "IC3") (pin "9") (pinfunction "SS/TR_9") (pintype "input"))
    )
    (net (code "46") (name "Net-(IC3-SW)") (class "Default")
      (node (ref "IC3") (pin "1") (pinfunction "SW_2_1") (pintype "output"))
      (node (ref "IC3") (pin "2") (pinfunction "SW_3_2") (pintype "output"))
      (node (ref "IC3") (pin "3") (pinfunction "SW_3") (pintype "output"))
      (node (ref "L2") (pin "2") (pinfunction "2_2") (pintype "power_in"))
    )
    (net (code "47") (name "SWD_SWCLK") (class "Default")
      (node (ref "IC1") (pin "49") (pinfunction "PA14_49") (pintype "bidirectional"))
      (node (ref "J3") (pin "2") (pinfunction "2_2") (pintype "bidirectional"))
    )
    (net (code "48") (name "SWD_SWDIO") (class "Default")
      (node (ref "IC1") (pin "46") (pinfunction "PA13_46") (pintype "bidirectional"))
      (node (ref "J3") (pin "5") (pinfunction "5_5") (pintype "bidirectional"))
    )
    (net (code "49") (name "USB_N") (class "Default")
      (node (ref "IC1") (pin "44") (pinfunction "PA11_44") (pintype "bidirectional"))
      (node (ref "J1") (pin "D-") (pinfunction "D-_D-") (pintype "bidirectional"))
    )
    (net (code "50") (name "USB_P") (class "Default")
      (node (ref "IC1") (pin "45") (pinfunction "PA12_45") (pintype "bidirectional"))
      (node (ref "J1") (pin "D+") (pinfunction "D+_D+") (pintype "bidirectional"))
    )
    (net (code "51") (name "VBAT_VSENSE") (class "Default")
      (node (ref "IC1") (pin "15") (pinfunction "PA1_15") (pintype "bidirectional"))
      (node (ref "R16") (pin "1") (pinfunction "1_1") (pintype "passive"))
      (node (ref "R17") (pin "2") (pinfunction "2_2") (pintype "passive"))
    )
    (net (code "52") (name "VDDA_FILTERED") (class "Default")
      (node (ref "C12") (pin "1") (pinfunction "1_1") (pintype "passive"))
      (node (ref "C16") (pin "1") (pinfunction "1_1") (pintype "passive"))
      (node (ref "IC1") (pin "13") (pinfunction "VDDA_13") (pintype "bidirectional"))
      (node (ref "L1") (pin "2") (pinfunction "2_2") (pintype "passive"))
    )
    (net (code "53") (name "V_BATT") (class "Default")
      (node (ref "C28") (pin "1") (pinfunction "1_1") (pintype "passive"))
      (node (ref "C32") (pin "1") (pinfunction "1_1") (pintype "passive"))
      (node (ref "D5") (pin "C") (pinfunction "C_C") (pintype "passive"))
      (node (ref "IC3") (pin "10") (pinfunction "AVIN_10") (pintype "input"))
      (node (ref "IC3") (pin "11") (pinfunction "PVIN_2_11") (pintype "input"))
      (node (ref "IC3") (pin "12") (pinfunction "PVIN_12") (pintype "input"))
      (node (ref "IC3") (pin "13") (pinfunction "EN_13") (pintype "input"))
      (node (ref "J2") (pin "P$2") (pinfunction "2_P$2") (pintype "passive"))
      (node (ref "R16") (pin "2") (pinfunction "2_2") (pintype "passive"))
    )
    (net (code "54") (name "XTAL_IN") (class "Default")
      (node (ref "C20") (pin "1") (pinfunction "1_1") (pintype "passive"))
      (node (ref "IC1") (pin "5") (pinfunction "PH0_5") (pintype "bidirectional"))
      (node (ref "X1") (pin "1") (pinfunction "1_1") (pintype "passive"))
    )
    (net (code "55") (name "XTAL_OUT") (class "Default")
      (node (ref "C21") (pin "1") (pinfunction "1_1") (pintype "passive"))
      (node (ref "IC1") (pin "6") (pinfunction "PH1_6") (pintype "bidirectional"))
      (node (ref "X1") (pin "3") (pinfunction "2_3") (pintype "passive"))
    )
    (net (code "56") (name "unconnected-(IC1-PA0_WKUP-Pad14)") (class "Default")
      (node (ref "IC1") (pin "14") (pinfunction "PA0_WKUP_14") (pintype "bidirectional"))
    )
    (net (code "57") (name "unconnected-(IC1-PA9-Pad42)") (class "Default")
      (node (ref "IC1") (pin "42") (pinfunction "PA9_42") (pintype "bidirectional"))
    )
    (net (code "58") (name "unconnected-(IC1-PA10-Pad43)") (class "Default")
      (node (ref "IC1") (pin "43") (pinfunction "PA10_43") (pintype "bidirectional"))
    )
    (net (code "59") (name "unconnected-(IC1-PA15-Pad50)") (class "Default")
      (node (ref "IC1") (pin "50") (pinfunction "PA15_50") (pintype "bidirectional"))
    )
    (net (code "60") (name "unconnected-(IC1-PB1-Pad27)") (class "Default")
      (node (ref "IC1") (pin "27") (pinfunction "PB1_27") (pintype "bidirectional"))
    )
    (net (code "61") (name "unconnected-(IC1-PB12-Pad33)") (class "Default")
      (node (ref "IC1") (pin "33") (pinfunction "PB12_33") (pintype "bidirectional"))
    )
    (net (code "62") (name "unconnected-(IC1-PB13-Pad34)") (class "Default")
      (node (ref "IC1") (pin "34") (pinfunction "PB13_34") (pintype "bidirectional"))
    )
    (net (code "63") (name "unconnected-(IC1-PB14-Pad35)") (class "Default")
      (node (ref "IC1") (pin "35") (pinfunction "PB14_35") (pintype "bidirectional"))
    )
    (net (code "64") (name "unconnected-(IC1-PB15-Pad36)") (class "Default")
      (node (ref "IC1") (pin "36") (pinfunction "PB15_36") (pintype "bidirectional"))
    )
    (net (code "65") (name "unconnected-(IC1-PC0-Pad8)") (class "Default")
      (node (ref "IC1") (pin "8") (pinfunction "PC0_8") (pintype "bidirectional"))
    )
    (net (code "66") (name "unconnected-(IC1-PC1-Pad9)") (class "Default")
      (node (ref "IC1") (pin "9") (pinfunction "PC1_9") (pintype "bidirectional"))
    )
    (net (code "67") (name "unconnected-(IC1-PC2-Pad10)") (class "Default")
      (node (ref "IC1") (pin "10") (pinfunction "PC2_10") (pintype "bidirectional"))
    )
    (net (code "68") (name "unconnected-(IC1-PC5-Pad25)") (class "Default")
      (node (ref "IC1") (pin "25") (pinfunction "PC5_25") (pintype "bidirectional"))
    )
    (net (code "69") (name "unconnected-(IC1-PC8-Pad39)") (class "Default")
      (node (ref "IC1") (pin "39") (pinfunction "PC8_39") (pintype "bidirectional"))
    )
    (net (code "70") (name "unconnected-(IC1-PC10-Pad51)") (class "Default")
      (node (ref "IC1") (pin "51") (pinfunction "PC10_51") (pintype "bidirectional"))
    )
    (net (code "71") (name "unconnected-(IC1-PC11-Pad52)") (class "Default")
      (node (ref "IC1") (pin "52") (pinfunction "PC11_52") (pintype "bidirectional"))
    )
    (net (code "72") (name "unconnected-(IC1-PC12-Pad53)") (class "Default")
      (node (ref "IC1") (pin "53") (pinfunction "PC12_53") (pintype "bidirectional"))
    )
    (net (code "73") (name "unconnected-(IC1-PC13-Pad2)") (class "Default")
      (node (ref "IC1") (pin "2") (pinfunction "PC13_2") (pintype "bidirectional"))
    )
    (net (code "74") (name "unconnected-(IC1-PC14-Pad3)") (class "Default")
      (node (ref "IC1") (pin "3") (pinfunction "PC14_3") (pintype "bidirectional"))
    )
    (net (code "75") (name "unconnected-(IC1-PC15-Pad4)") (class "Default")
      (node (ref "IC1") (pin "4") (pinfunction "PC15_4") (pintype "bidirectional"))
    )
    (net (code "76") (name "unconnected-(IC2-1_SAFEBOOT_N-Pad1)") (class "Default")
      (node (ref "IC2") (pin "1") (pinfunction "1_SAFEBOOT_N_1") (pintype "bidirectional"))
    )
    (net (code "77") (name "unconnected-(IC2-2_D_SEL-Pad2)") (class "Default")
      (node (ref "IC2") (pin "2") (pinfunction "2_D_SEL_2") (pintype "bidirectional"))
    )
    (net (code "78") (name "unconnected-(IC2-4_EXTINT-Pad4)") (class "Default")
      (node (ref "IC2") (pin "4") (pinfunction "4_EXTINT_4") (pintype "bidirectional"))
    )
    (net (code "79") (name "unconnected-(IC2-5_USB_DM-Pad5)") (class "Default")
      (node (ref "IC2") (pin "5") (pinfunction "5_USB_DM_5") (pintype "bidirectional"))
    )
    (net (code "80") (name "unconnected-(IC2-6_USB_DP-Pad6)") (class "Default")
      (node (ref "IC2") (pin "6") (pinfunction "6_USB_DP_6") (pintype "bidirectional"))
    )
    (net (code "81") (name "unconnected-(IC2-7_VDD_USB-Pad7)") (class "Default")
      (node (ref "IC2") (pin "7") (pinfunction "7_VDD_USB_7") (pintype "bidirectional"))
    )
    (net (code "82") (name "unconnected-(IC2-14_LNA_EN{slash}RESERVED-Pad14)") (class "Default")
      (node (ref "IC2") (pin "14") (pinfunction "14_LNA_EN/RESERVED_14") (pintype "bidirectional"))
    )
    (net (code "83") (name "unconnected-(IC2-15_RESERVED-Pad15)") (class "Default")
      (node (ref "IC2") (pin "15") (pinfunction "15_RESERVED_15") (pintype "bidirectional"))
    )
    (net (code "84") (name "unconnected-(IC2-16_RESERVED-Pad16)") (class "Default")
      (node (ref "IC2") (pin "16") (pinfunction "16_RESERVED_16") (pintype "bidirectional"))
    )
    (net (code "85") (name "unconnected-(IC2-17_RESERVED-Pad17)") (class "Default")
      (node (ref "IC2") (pin "17") (pinfunction "17_RESERVED_17") (pintype "bidirectional"))
    )
    (net (code "86") (name "unconnected-(IC2-18_SDA{slash}SPI_CS_N-Pad18)") (class "Default")
      (node (ref "IC2") (pin "18") (pinfunction "18_SDA/SPI_CS_N_18") (pintype "bidirectional"))
    )
    (net (code "87") (name "unconnected-(IC2-19_SCL{slash}SPI_CLK-Pad19)") (class "Default")
      (node (ref "IC2") (pin "19") (pinfunction "19_SCL/SPI_CLK_19") (pintype "bidirectional"))
    )
    (net (code "88") (name "unconnected-(J1-PadID)") (class "Default")
      (node (ref "J1") (pin "ID") (pinfunction "ID_ID") (pintype "bidirectional"))
    )
    (net (code "89") (name "unconnected-(J1-PadVBUS)") (class "Default")
      (node (ref "J1") (pin "VBUS") (pinfunction "VBUS_VBUS") (pintype "power_in"))
    )
  )
)
